# pcblayout.net
KiCad netlist of a schematic drawn in Altium Designer
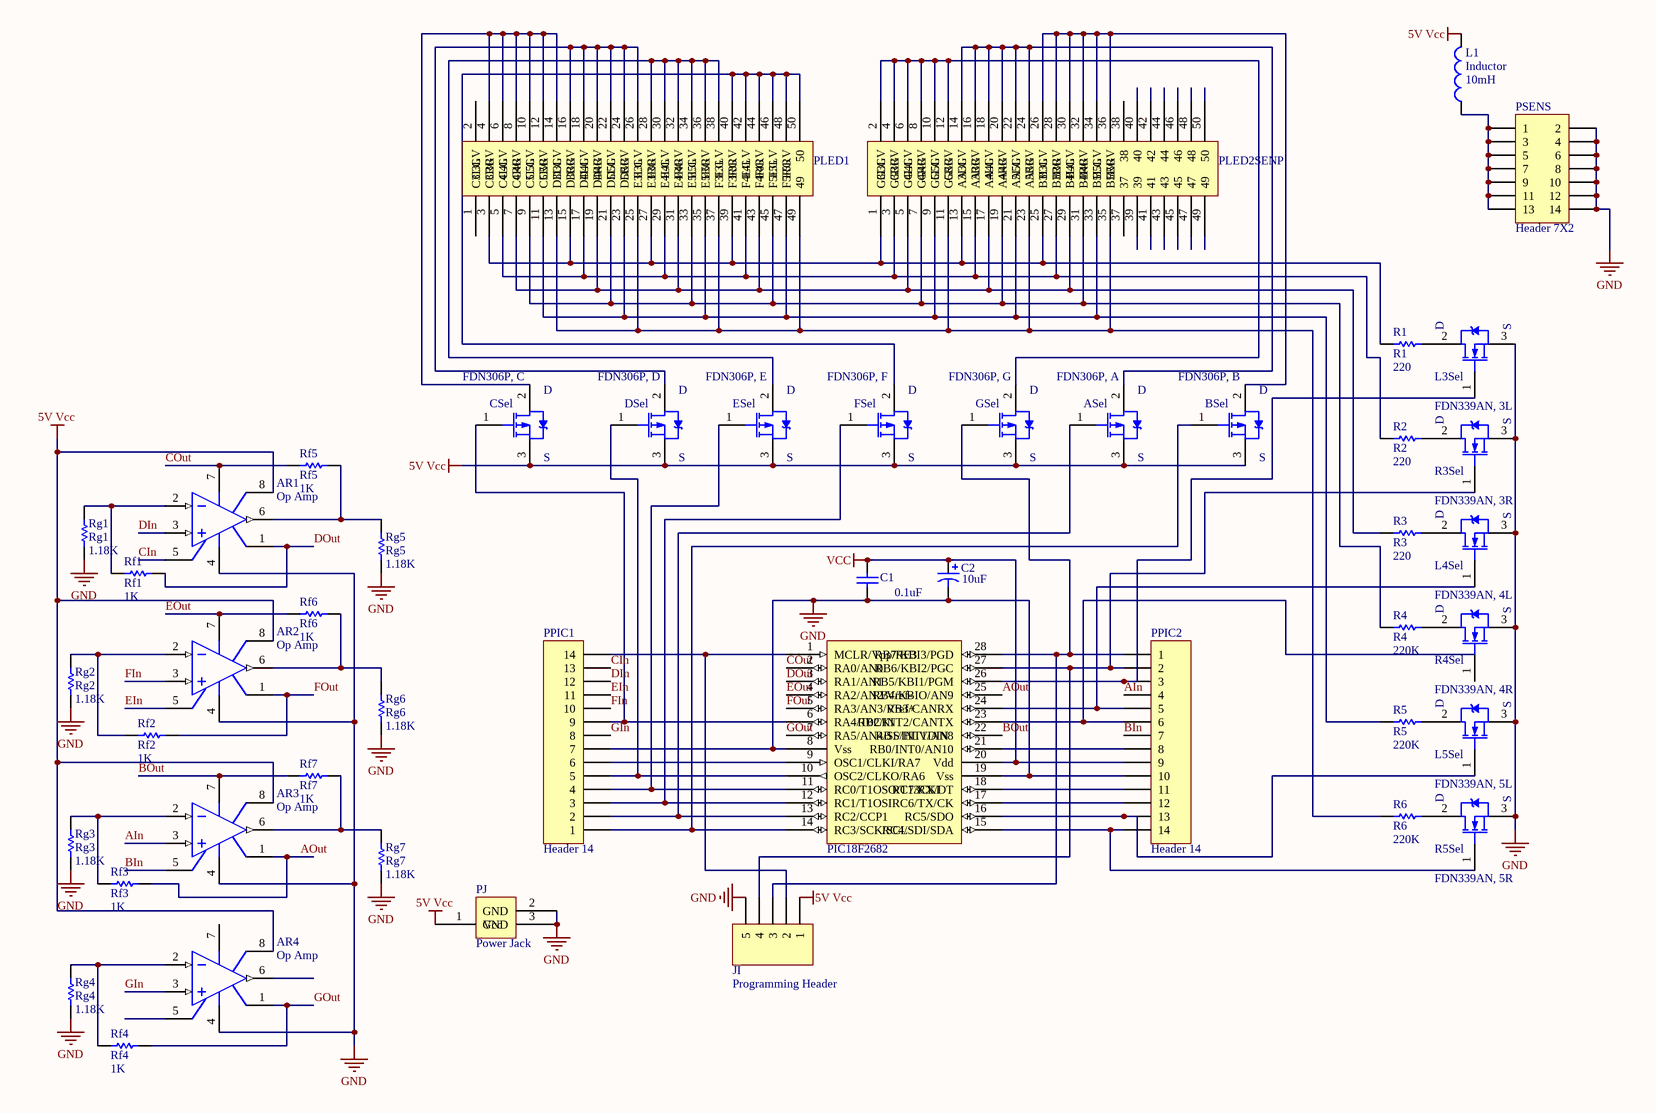
[diagram p0: pcblayout.SchDoc]

(export (version "E")
  (design (tool "Eeschema 10.0.6"))
  (components
    (comp (ref "AR1")
      (value "Op Amp")
      (footprint "SOIC127P600X175-8N")
      (description "FET Operational Amplifier")
      (fields (field (name "PUBLISHER") "Altium Limited"))
      (libsource (lib "Miscellaneous Devices") (part "Op Amp"))
    )
    (comp (ref "AR2")
      (value "Op Amp")
      (footprint "SOIC127P600X175-8N")
      (description "FET Operational Amplifier")
      (fields (field (name "PUBLISHER") "Altium Limited"))
      (libsource (lib "Miscellaneous Devices") (part "Op Amp"))
    )
    (comp (ref "AR3")
      (value "Op Amp")
      (footprint "SOIC127P600X175-8N")
      (description "FET Operational Amplifier")
      (fields (field (name "PUBLISHER") "Altium Limited"))
      (libsource (lib "Miscellaneous Devices") (part "Op Amp"))
    )
    (comp (ref "AR4")
      (value "Op Amp")
      (footprint "SOIC127P600X175-8N")
      (description "FET Operational Amplifier")
      (fields (field (name "PUBLISHER") "Altium Limited"))
      (libsource (lib "Miscellaneous Devices") (part "Op Amp"))
    )
    (comp (ref "ASel")
      (value "FDN306P, A")
      (footprint "SOT23-3M")
      (description "Pch MOSFET")
      (libsource (lib "pcbLib") (part "FDN304P"))
    )
    (comp (ref "BSel")
      (value "FDN306P, B")
      (footprint "SOT23-3M")
      (description "Pch MOSFET")
      (libsource (lib "pcbLib") (part "FDN304P"))
    )
    (comp (ref "C1")
      (value "0.1uF")
      (footprint "CAPC2012M")
      (description "Capacitor")
      (fields (field (name "Comment") "Cap") (field (name "PUBLISHER") "Altium Limited"))
      (libsource (lib "Miscellaneous Devices") (part "Cap"))
    )
    (comp (ref "C2")
      (value "10uF")
      (footprint "TC3216-1206")
      (description "Polarized Capacitor (Radial)")
      (fields (field (name "Comment") "Cap Pol1") (field (name "PUBLISHER") "Altium Limited"))
      (libsource (lib "Miscellaneous Devices") (part "Cap Pol1"))
    )
    (comp (ref "CSel")
      (value "FDN306P, C")
      (footprint "SOT23-3M")
      (description "Pch MOSFET")
      (libsource (lib "pcbLib") (part "FDN304P"))
    )
    (comp (ref "DSel")
      (value "FDN306P, D")
      (footprint "SOT23-3M")
      (description "Pch MOSFET")
      (libsource (lib "pcbLib") (part "FDN304P"))
    )
    (comp (ref "ESel")
      (value "FDN306P, E")
      (footprint "SOT23-3M")
      (description "Pch MOSFET")
      (libsource (lib "pcbLib") (part "FDN304P"))
    )
    (comp (ref "FSel")
      (value "FDN306P, F")
      (footprint "SOT23-3M")
      (description "Pch MOSFET")
      (libsource (lib "pcbLib") (part "FDN304P"))
    )
    (comp (ref "GSel")
      (value "FDN306P, G")
      (footprint "SOT23-3M")
      (description "Pch MOSFET")
      (libsource (lib "pcbLib") (part "FDN304P"))
    )
    (comp (ref "JI")
      (value "Programming Header")
      (footprint "HDR1X5")
      (description "Header, 5-Pin")
      (fields (field (name "PUBLISHER") "Altium Limited"))
      (libsource (lib "Miscellaneous Connectors") (part "Header 5"))
    )
    (comp (ref "L1")
      (value "Inductor")
      (footprint "INDC2012M")
      (fields (field (name "ALTIUM_VALUE") "10mH") (field (name "PUBLISHER") "Altium Limited"))
      (libsource (lib "Miscellaneous Devices") (part "Inductor"))
    )
    (comp (ref "L3Sel")
      (value "FDN339AN, 3L")
      (footprint "SOT23-3M")
      (description "Nch MOSFET")
      (libsource (lib "pcbLib") (part "FDN339AN"))
    )
    (comp (ref "L4Sel")
      (value "FDN339AN, 4L")
      (footprint "SOT23-3M")
      (description "Nch MOSFET")
      (libsource (lib "pcbLib") (part "FDN339AN"))
    )
    (comp (ref "L5Sel")
      (value "FDN339AN, 5L")
      (footprint "SOT23-3M")
      (description "Nch MOSFET")
      (libsource (lib "pcbLib") (part "FDN339AN"))
    )
    (comp (ref "PIC18F2682")
      (value "PIC18F2682")
      (footprint "DIP28")
      (libsource (lib "pcbLib") (part "PIC18F2682"))
    )
    (comp (ref "PJ")
      (value "Power Jack")
      (footprint "BARREL JACK")
      (libsource (lib "pcbLib") (part "Power Jack"))
    )
    (comp (ref "PLED1")
      (value "50x2 Pin Header, PLED1")
      (footprint "HDR2X25")
      (libsource (lib "pcbLib") (part "50x2 Pin Header, PLED1"))
    )
    (comp (ref "PLED2SENP")
      (value "50x2 Pin Header, PLED2SENP")
      (footprint "HDR2X25")
      (libsource (lib "pcbLib") (part "50x2 Pin Header, PLED2SENP"))
    )
    (comp (ref "PPIC1")
      (value "Header 14")
      (footprint "HDR1X14")
      (description "Header, 14-Pin")
      (fields (field (name "PUBLISHER") "Altium Limited"))
      (libsource (lib "") (part "Header 14_1"))
    )
    (comp (ref "PPIC2")
      (value "Header 14")
      (footprint "HDR1X14")
      (description "Header, 14-Pin")
      (fields (field (name "PUBLISHER") "Altium Limited"))
      (libsource (lib "Miscellaneous Connectors") (part "Header 14"))
    )
    (comp (ref "PSENS")
      (value "Header 7X2")
      (footprint "HDR2X7")
      (description "Header, 7-Pin, Dual row")
      (fields (field (name "PUBLISHER") "Altium Limited"))
      (libsource (lib "Miscellaneous Connectors") (part "Header 7X2"))
    )
    (comp (ref "R1")
      (value "R1")
      (footprint "RESC2012M")
      (description "Resistor")
      (fields (field (name "ALTIUM_VALUE") "220") (field (name "PUBLISHER") "Altium Limited"))
      (libsource (lib "Miscellaneous Devices") (part "Res1"))
    )
    (comp (ref "R2")
      (value "R2")
      (footprint "RESC2012M")
      (description "Resistor")
      (fields (field (name "ALTIUM_VALUE") "220") (field (name "PUBLISHER") "Altium Limited"))
      (libsource (lib "Miscellaneous Devices") (part "Res1"))
    )
    (comp (ref "R3")
      (value "R3")
      (footprint "RESC2012M")
      (description "Resistor")
      (fields (field (name "ALTIUM_VALUE") "220") (field (name "PUBLISHER") "Altium Limited"))
      (libsource (lib "Miscellaneous Devices") (part "Res1"))
    )
    (comp (ref "R3Sel")
      (value "FDN339AN, 3R")
      (footprint "SOT23-3M")
      (description "Nch MOSFET")
      (libsource (lib "pcbLib") (part "FDN339AN"))
    )
    (comp (ref "R4")
      (value "R4")
      (footprint "RESC2012M")
      (description "Resistor")
      (fields (field (name "ALTIUM_VALUE") "220K") (field (name "PUBLISHER") "Altium Limited"))
      (libsource (lib "Miscellaneous Devices") (part "Res1"))
    )
    (comp (ref "R4Sel")
      (value "FDN339AN, 4R")
      (footprint "SOT23-3M")
      (description "Nch MOSFET")
      (libsource (lib "pcbLib") (part "FDN339AN"))
    )
    (comp (ref "R5")
      (value "R5")
      (footprint "RESC2012M")
      (description "Resistor")
      (fields (field (name "ALTIUM_VALUE") "220K") (field (name "PUBLISHER") "Altium Limited"))
      (libsource (lib "Miscellaneous Devices") (part "Res1"))
    )
    (comp (ref "R5Sel")
      (value "FDN339AN, 5R")
      (footprint "SOT23-3M")
      (description "Nch MOSFET")
      (libsource (lib "pcbLib") (part "FDN339AN"))
    )
    (comp (ref "R6")
      (value "R6")
      (footprint "RESC2012M")
      (description "Resistor")
      (fields (field (name "ALTIUM_VALUE") "220K") (field (name "PUBLISHER") "Altium Limited"))
      (libsource (lib "Miscellaneous Devices") (part "Res1"))
    )
    (comp (ref "Rf1")
      (value "Rf1")
      (footprint "RESC2012M")
      (description "Resistor")
      (fields (field (name "ALTIUM_VALUE") "1K") (field (name "PUBLISHER") "Altium Limited"))
      (libsource (lib "Miscellaneous Devices") (part "Res1"))
    )
    (comp (ref "Rf2")
      (value "Rf2")
      (footprint "RESC2012M")
      (description "Resistor")
      (fields (field (name "ALTIUM_VALUE") "1K") (field (name "PUBLISHER") "Altium Limited"))
      (libsource (lib "Miscellaneous Devices") (part "Res1"))
    )
    (comp (ref "Rf3")
      (value "Rf3")
      (footprint "RESC2012M")
      (description "Resistor")
      (fields (field (name "ALTIUM_VALUE") "1K") (field (name "PUBLISHER") "Altium Limited"))
      (libsource (lib "Miscellaneous Devices") (part "Res1"))
    )
    (comp (ref "Rf4")
      (value "Rf4")
      (footprint "RESC2012M")
      (description "Resistor")
      (fields (field (name "ALTIUM_VALUE") "1K") (field (name "PUBLISHER") "Altium Limited"))
      (libsource (lib "Miscellaneous Devices") (part "Res1"))
    )
    (comp (ref "Rf5")
      (value "Rf5")
      (footprint "RESC2012M")
      (description "Resistor")
      (fields (field (name "ALTIUM_VALUE") "1K") (field (name "PUBLISHER") "Altium Limited"))
      (libsource (lib "Miscellaneous Devices") (part "Res1"))
    )
    (comp (ref "Rf6")
      (value "Rf6")
      (footprint "RESC2012M")
      (description "Resistor")
      (fields (field (name "ALTIUM_VALUE") "1K") (field (name "PUBLISHER") "Altium Limited"))
      (libsource (lib "Miscellaneous Devices") (part "Res1"))
    )
    (comp (ref "Rf7")
      (value "Rf7")
      (footprint "RESC2012M")
      (description "Resistor")
      (fields (field (name "ALTIUM_VALUE") "1K") (field (name "PUBLISHER") "Altium Limited"))
      (libsource (lib "Miscellaneous Devices") (part "Res1"))
    )
    (comp (ref "Rg1")
      (value "Rg1")
      (footprint "RESC2012M")
      (description "Resistor")
      (fields (field (name "ALTIUM_VALUE") "1.18K") (field (name "PUBLISHER") "Altium Limited"))
      (libsource (lib "Miscellaneous Devices") (part "Res1"))
    )
    (comp (ref "Rg2")
      (value "Rg2")
      (footprint "RESC2012M")
      (description "Resistor")
      (fields (field (name "ALTIUM_VALUE") "1.18K") (field (name "PUBLISHER") "Altium Limited"))
      (libsource (lib "Miscellaneous Devices") (part "Res1"))
    )
    (comp (ref "Rg3")
      (value "Rg3")
      (footprint "RESC2012M")
      (description "Resistor")
      (fields (field (name "ALTIUM_VALUE") "1.18K") (field (name "PUBLISHER") "Altium Limited"))
      (libsource (lib "Miscellaneous Devices") (part "Res1"))
    )
    (comp (ref "Rg4")
      (value "Rg4")
      (footprint "RESC2012M")
      (description "Resistor")
      (fields (field (name "ALTIUM_VALUE") "1.18K") (field (name "PUBLISHER") "Altium Limited"))
      (libsource (lib "Miscellaneous Devices") (part "Res1"))
    )
    (comp (ref "Rg5")
      (value "Rg5")
      (footprint "RESC2012M")
      (description "Resistor")
      (fields (field (name "ALTIUM_VALUE") "1.18K") (field (name "PUBLISHER") "Altium Limited"))
      (libsource (lib "Miscellaneous Devices") (part "Res1"))
    )
    (comp (ref "Rg6")
      (value "Rg6")
      (footprint "RESC2012M")
      (description "Resistor")
      (fields (field (name "ALTIUM_VALUE") "1.18K") (field (name "PUBLISHER") "Altium Limited"))
      (libsource (lib "Miscellaneous Devices") (part "Res1"))
    )
    (comp (ref "Rg7")
      (value "Rg7")
      (footprint "RESC2012M")
      (description "Resistor")
      (fields (field (name "ALTIUM_VALUE") "1.18K") (field (name "PUBLISHER") "Altium Limited"))
      (libsource (lib "Miscellaneous Devices") (part "Res1"))
    )
  )
  (nets
    (net (code "1") (name "/AIn") (class "Default")
      (node (ref "AR3") (pin "3") (pinfunction "IN+_3") (pintype "input"))
      (node (ref "PPIC2") (pin "4") (pinfunction "4_4") (pintype "passive"))
    )
    (net (code "2") (name "/AOut") (class "Default")
      (node (ref "AR3") (pin "1") (pinfunction "OS_NUL_1") (pintype "passive"))
      (node (ref "PIC18F2682") (pin "25") (pinfunction "RB4/KBIO/AN9_25") (pintype "bidirectional"))
      (node (ref "Rf3") (pin "2") (pinfunction "2_2") (pintype "passive"))
    )
    (net (code "3") (name "/BIn") (class "Default")
      (node (ref "AR3") (pin "5") (pinfunction "OS_NUL_5") (pintype "passive"))
      (node (ref "PPIC2") (pin "7") (pinfunction "7_7") (pintype "passive"))
    )
    (net (code "4") (name "/BOut") (class "Default")
      (node (ref "AR3") (pin "7") (pinfunction "V+_7") (pintype "power_in"))
      (node (ref "PIC18F2682") (pin "22") (pinfunction "RB1/INT1/AN8_22") (pintype "bidirectional"))
      (node (ref "Rf7") (pin "1") (pinfunction "1_1") (pintype "passive"))
    )
    (net (code "5") (name "/CIn") (class "Default")
      (node (ref "AR1") (pin "5") (pinfunction "OS_NUL_5") (pintype "passive"))
      (node (ref "PPIC1") (pin "13") (pinfunction "13_13") (pintype "passive"))
    )
    (net (code "6") (name "/COut") (class "Default")
      (node (ref "AR1") (pin "7") (pinfunction "V+_7") (pintype "power_in"))
      (node (ref "PIC18F2682") (pin "2") (pinfunction "RA0/AN0_2") (pintype "bidirectional"))
      (node (ref "Rf5") (pin "1") (pinfunction "1_1") (pintype "passive"))
    )
    (net (code "7") (name "/DIn") (class "Default")
      (node (ref "AR1") (pin "3") (pinfunction "IN+_3") (pintype "input"))
      (node (ref "PPIC1") (pin "12") (pinfunction "12_12") (pintype "passive"))
    )
    (net (code "8") (name "/DOut") (class "Default")
      (node (ref "AR1") (pin "1") (pinfunction "OS_NUL_1") (pintype "passive"))
      (node (ref "PIC18F2682") (pin "3") (pinfunction "RA1/AN1_3") (pintype "bidirectional"))
      (node (ref "Rf1") (pin "2") (pinfunction "2_2") (pintype "passive"))
    )
    (net (code "9") (name "/EIn") (class "Default")
      (node (ref "AR2") (pin "5") (pinfunction "OS_NUL_5") (pintype "passive"))
      (node (ref "PPIC1") (pin "11") (pinfunction "11_11") (pintype "passive"))
    )
    (net (code "10") (name "/EOut") (class "Default")
      (node (ref "AR2") (pin "7") (pinfunction "V+_7") (pintype "power_in"))
      (node (ref "PIC18F2682") (pin "4") (pinfunction "RA2/AN2/Vref-_4") (pintype "bidirectional"))
      (node (ref "Rf6") (pin "1") (pinfunction "1_1") (pintype "passive"))
    )
    (net (code "11") (name "/FIn") (class "Default")
      (node (ref "AR2") (pin "3") (pinfunction "IN+_3") (pintype "input"))
      (node (ref "PPIC1") (pin "10") (pinfunction "10_10") (pintype "passive"))
    )
    (net (code "12") (name "/FOut") (class "Default")
      (node (ref "AR2") (pin "1") (pinfunction "OS_NUL_1") (pintype "passive"))
      (node (ref "PIC18F2682") (pin "5") (pinfunction "RA3/AN3/Vref+_5") (pintype "bidirectional"))
      (node (ref "Rf2") (pin "2") (pinfunction "2_2") (pintype "passive"))
    )
    (net (code "13") (name "/GIn") (class "Default")
      (node (ref "AR4") (pin "3") (pinfunction "IN+_3") (pintype "input"))
      (node (ref "PPIC1") (pin "8") (pinfunction "8_8") (pintype "passive"))
    )
    (net (code "14") (name "/GOut") (class "Default")
      (node (ref "AR4") (pin "1") (pinfunction "OS_NUL_1") (pintype "passive"))
      (node (ref "PIC18F2682") (pin "7") (pinfunction "RA5/AN4/SS/HLVDIN_7") (pintype "bidirectional"))
      (node (ref "Rf4") (pin "2") (pinfunction "2_2") (pintype "passive"))
    )
    (net (code "15") (name "5V Vcc") (class "Default")
      (node (ref "AR1") (pin "8") (pinfunction "TAB_8") (pintype "passive"))
      (node (ref "AR2") (pin "8") (pinfunction "TAB_8") (pintype "passive"))
      (node (ref "AR3") (pin "8") (pinfunction "TAB_8") (pintype "passive"))
      (node (ref "AR4") (pin "8") (pinfunction "TAB_8") (pintype "passive"))
      (node (ref "ASel") (pin "3") (pinfunction "S_3") (pintype "passive"))
      (node (ref "BSel") (pin "3") (pinfunction "S_3") (pintype "passive"))
      (node (ref "CSel") (pin "3") (pinfunction "S_3") (pintype "passive"))
      (node (ref "DSel") (pin "3") (pinfunction "S_3") (pintype "passive"))
      (node (ref "ESel") (pin "3") (pinfunction "S_3") (pintype "passive"))
      (node (ref "FSel") (pin "3") (pinfunction "S_3") (pintype "passive"))
      (node (ref "GSel") (pin "3") (pinfunction "S_3") (pintype "passive"))
      (node (ref "JI") (pin "1") (pinfunction "1_1") (pintype "passive"))
      (node (ref "L1") (pin "2") (pinfunction "2_2") (pintype "passive"))
      (node (ref "PJ") (pin "1") (pinfunction "Vcc_1") (pintype "passive"))
    )
    (net (code "16") (name "GND") (class "Default")
      (node (ref "AR1") (pin "4") (pinfunction "V-_4") (pintype "power_in"))
      (node (ref "AR2") (pin "4") (pinfunction "V-_4") (pintype "power_in"))
      (node (ref "AR3") (pin "4") (pinfunction "V-_4") (pintype "power_in"))
      (node (ref "AR4") (pin "4") (pinfunction "V-_4") (pintype "power_in"))
      (node (ref "C1") (pin "1") (pinfunction "1_1") (pintype "passive"))
      (node (ref "C2") (pin "2") (pinfunction "2_2") (pintype "passive"))
      (node (ref "JI") (pin "5") (pinfunction "5_5") (pintype "passive"))
      (node (ref "L3Sel") (pin "3") (pinfunction "S_3") (pintype "passive"))
      (node (ref "L4Sel") (pin "3") (pinfunction "S_3") (pintype "passive"))
      (node (ref "L5Sel") (pin "3") (pinfunction "S_3") (pintype "passive"))
      (node (ref "PIC18F2682") (pin "19") (pinfunction "Vss_19") (pintype "power_in"))
      (node (ref "PIC18F2682") (pin "8") (pinfunction "Vss_8") (pintype "power_in"))
      (node (ref "PJ") (pin "2") (pinfunction "GND_2") (pintype "passive"))
      (node (ref "PJ") (pin "3") (pinfunction "GND_3") (pintype "passive"))
      (node (ref "PPIC1") (pin "7") (pinfunction "7_7") (pintype "passive"))
      (node (ref "PPIC2") (pin "10") (pinfunction "10_10") (pintype "passive"))
      (node (ref "PSENS") (pin "10") (pinfunction "10_10") (pintype "passive"))
      (node (ref "PSENS") (pin "12") (pinfunction "12_12") (pintype "passive"))
      (node (ref "PSENS") (pin "14") (pinfunction "14_14") (pintype "passive"))
      (node (ref "PSENS") (pin "2") (pinfunction "2_2") (pintype "passive"))
      (node (ref "PSENS") (pin "4") (pinfunction "4_4") (pintype "passive"))
      (node (ref "PSENS") (pin "6") (pinfunction "6_6") (pintype "passive"))
      (node (ref "PSENS") (pin "8") (pinfunction "8_8") (pintype "passive"))
      (node (ref "R3Sel") (pin "3") (pinfunction "S_3") (pintype "passive"))
      (node (ref "R4Sel") (pin "3") (pinfunction "S_3") (pintype "passive"))
      (node (ref "R5Sel") (pin "3") (pinfunction "S_3") (pintype "passive"))
      (node (ref "Rg1") (pin "1") (pinfunction "1_1") (pintype "passive"))
      (node (ref "Rg2") (pin "2") (pinfunction "2_2") (pintype "passive"))
      (node (ref "Rg3") (pin "1") (pinfunction "1_1") (pintype "passive"))
      (node (ref "Rg4") (pin "1") (pinfunction "1_1") (pintype "passive"))
      (node (ref "Rg5") (pin "1") (pinfunction "1_1") (pintype "passive"))
      (node (ref "Rg6") (pin "1") (pinfunction "1_1") (pintype "passive"))
      (node (ref "Rg7") (pin "1") (pinfunction "1_1") (pintype "passive"))
    )
    (net (code "17") (name "Net-(AR1-IN-)") (class "Default")
      (node (ref "AR1") (pin "2") (pinfunction "IN-_2") (pintype "input"))
      (node (ref "Rf1") (pin "1") (pinfunction "1_1") (pintype "passive"))
      (node (ref "Rg1") (pin "2") (pinfunction "2_2") (pintype "passive"))
    )
    (net (code "18") (name "Net-(AR1-OUT)") (class "Default")
      (node (ref "AR1") (pin "6") (pinfunction "OUT_6") (pintype "output"))
      (node (ref "Rf5") (pin "2") (pinfunction "2_2") (pintype "passive"))
      (node (ref "Rg5") (pin "2") (pinfunction "2_2") (pintype "passive"))
    )
    (net (code "19") (name "Net-(AR2-IN-)") (class "Default")
      (node (ref "AR2") (pin "2") (pinfunction "IN-_2") (pintype "input"))
      (node (ref "Rf2") (pin "1") (pinfunction "1_1") (pintype "passive"))
      (node (ref "Rg2") (pin "1") (pinfunction "1_1") (pintype "passive"))
    )
    (net (code "20") (name "Net-(AR2-OUT)") (class "Default")
      (node (ref "AR2") (pin "6") (pinfunction "OUT_6") (pintype "output"))
      (node (ref "Rf6") (pin "2") (pinfunction "2_2") (pintype "passive"))
      (node (ref "Rg6") (pin "2") (pinfunction "2_2") (pintype "passive"))
    )
    (net (code "21") (name "Net-(AR3-IN-)") (class "Default")
      (node (ref "AR3") (pin "2") (pinfunction "IN-_2") (pintype "input"))
      (node (ref "Rf3") (pin "1") (pinfunction "1_1") (pintype "passive"))
      (node (ref "Rg3") (pin "2") (pinfunction "2_2") (pintype "passive"))
    )
    (net (code "22") (name "Net-(AR3-OUT)") (class "Default")
      (node (ref "AR3") (pin "6") (pinfunction "OUT_6") (pintype "output"))
      (node (ref "Rf7") (pin "2") (pinfunction "2_2") (pintype "passive"))
      (node (ref "Rg7") (pin "2") (pinfunction "2_2") (pintype "passive"))
    )
    (net (code "23") (name "Net-(AR4-IN-)") (class "Default")
      (node (ref "AR4") (pin "2") (pinfunction "IN-_2") (pintype "input"))
      (node (ref "Rf4") (pin "1") (pinfunction "1_1") (pintype "passive"))
      (node (ref "Rg4") (pin "2") (pinfunction "2_2") (pintype "passive"))
    )
    (net (code "24") (name "Net-(ASel-D)") (class "Default")
      (node (ref "ASel") (pin "2") (pinfunction "D_2") (pintype "passive"))
      (node (ref "PLED2SENP") (pin "14") (pinfunction "A3LV_14") (pintype "passive"))
      (node (ref "PLED2SENP") (pin "16") (pinfunction "A3RV_16") (pintype "passive"))
      (node (ref "PLED2SENP") (pin "18") (pinfunction "A4LV_18") (pintype "passive"))
      (node (ref "PLED2SENP") (pin "20") (pinfunction "A4RV_20") (pintype "passive"))
      (node (ref "PLED2SENP") (pin "22") (pinfunction "A5LV_22") (pintype "passive"))
      (node (ref "PLED2SENP") (pin "24") (pinfunction "A5RV_24") (pintype "passive"))
    )
    (net (code "25") (name "Net-(ASel-G)") (class "Default")
      (node (ref "ASel") (pin "1") (pinfunction "G_1") (pintype "passive"))
      (node (ref "PIC18F2682") (pin "13") (pinfunction "RC2/CCP1_13") (pintype "bidirectional"))
      (node (ref "PPIC1") (pin "2") (pinfunction "2_2") (pintype "passive"))
    )
    (net (code "26") (name "Net-(BSel-D)") (class "Default")
      (node (ref "BSel") (pin "2") (pinfunction "D_2") (pintype "passive"))
      (node (ref "PLED2SENP") (pin "26") (pinfunction "B3LV_26") (pintype "passive"))
      (node (ref "PLED2SENP") (pin "28") (pinfunction "B3RV_28") (pintype "passive"))
      (node (ref "PLED2SENP") (pin "30") (pinfunction "B4LV_30") (pintype "passive"))
      (node (ref "PLED2SENP") (pin "32") (pinfunction "B4RV_32") (pintype "passive"))
      (node (ref "PLED2SENP") (pin "34") (pinfunction "B5LV_34") (pintype "passive"))
      (node (ref "PLED2SENP") (pin "36") (pinfunction "B5RV_36") (pintype "passive"))
    )
    (net (code "27") (name "Net-(BSel-G)") (class "Default")
      (node (ref "BSel") (pin "1") (pinfunction "G_1") (pintype "passive"))
      (node (ref "PIC18F2682") (pin "14") (pinfunction "RC3/SCK/SCL_14") (pintype "bidirectional"))
      (node (ref "PPIC1") (pin "1") (pinfunction "1_1") (pintype "passive"))
    )
    (net (code "28") (name "Net-(CSel-D)") (class "Default")
      (node (ref "CSel") (pin "2") (pinfunction "D_2") (pintype "passive"))
      (node (ref "PLED1") (pin "10") (pinfunction "C5LV_10") (pintype "passive"))
      (node (ref "PLED1") (pin "12") (pinfunction "C5RV_12") (pintype "passive"))
      (node (ref "PLED1") (pin "14") (pinfunction "D3LV_14") (pintype "passive"))
      (node (ref "PLED1") (pin "4") (pinfunction "C3RV_4") (pintype "passive"))
      (node (ref "PLED1") (pin "6") (pinfunction "C4LV_6") (pintype "passive"))
      (node (ref "PLED1") (pin "8") (pinfunction "C4RV_8") (pintype "passive"))
    )
    (net (code "29") (name "Net-(CSel-G)") (class "Default")
      (node (ref "CSel") (pin "1") (pinfunction "G_1") (pintype "passive"))
      (node (ref "PIC18F2682") (pin "6") (pinfunction "RA4/T0CKI_6") (pintype "bidirectional"))
      (node (ref "PPIC1") (pin "9") (pinfunction "9_9") (pintype "passive"))
    )
    (net (code "30") (name "Net-(DSel-D)") (class "Default")
      (node (ref "DSel") (pin "2") (pinfunction "D_2") (pintype "passive"))
      (node (ref "PLED1") (pin "16") (pinfunction "D3RV_16") (pintype "passive"))
      (node (ref "PLED1") (pin "18") (pinfunction "D4LV_18") (pintype "passive"))
      (node (ref "PLED1") (pin "20") (pinfunction "D4RV_20") (pintype "passive"))
      (node (ref "PLED1") (pin "22") (pinfunction "D5LV_22") (pintype "passive"))
      (node (ref "PLED1") (pin "24") (pinfunction "D5RV_24") (pintype "passive"))
      (node (ref "PLED1") (pin "26") (pinfunction "E3LV_26") (pintype "passive"))
    )
    (net (code "31") (name "Net-(DSel-G)") (class "Default")
      (node (ref "DSel") (pin "1") (pinfunction "G_1") (pintype "passive"))
      (node (ref "PIC18F2682") (pin "10") (pinfunction "OSC2/CLKO/RA6_10") (pintype "output"))
      (node (ref "PPIC1") (pin "5") (pinfunction "5_5") (pintype "passive"))
    )
    (net (code "32") (name "Net-(ESel-D)") (class "Default")
      (node (ref "ESel") (pin "2") (pinfunction "D_2") (pintype "passive"))
      (node (ref "PLED1") (pin "28") (pinfunction "E3RV_28") (pintype "passive"))
      (node (ref "PLED1") (pin "30") (pinfunction "E4LV_30") (pintype "passive"))
      (node (ref "PLED1") (pin "32") (pinfunction "E4RV_32") (pintype "passive"))
      (node (ref "PLED1") (pin "34") (pinfunction "E5LV_34") (pintype "passive"))
      (node (ref "PLED1") (pin "36") (pinfunction "E5RV_36") (pintype "passive"))
      (node (ref "PLED1") (pin "38") (pinfunction "F3LV_38") (pintype "passive"))
    )
    (net (code "33") (name "Net-(ESel-G)") (class "Default")
      (node (ref "ESel") (pin "1") (pinfunction "G_1") (pintype "passive"))
      (node (ref "PIC18F2682") (pin "11") (pinfunction "RC0/T1OSO/T13CKI_11") (pintype "bidirectional"))
      (node (ref "PPIC1") (pin "4") (pinfunction "4_4") (pintype "passive"))
    )
    (net (code "34") (name "Net-(FSel-D)") (class "Default")
      (node (ref "FSel") (pin "2") (pinfunction "D_2") (pintype "passive"))
      (node (ref "PLED1") (pin "40") (pinfunction "F3RV_40") (pintype "passive"))
      (node (ref "PLED1") (pin "42") (pinfunction "F4LV_42") (pintype "passive"))
      (node (ref "PLED1") (pin "44") (pinfunction "F4RV_44") (pintype "passive"))
      (node (ref "PLED1") (pin "46") (pinfunction "F5LV_46") (pintype "passive"))
      (node (ref "PLED1") (pin "48") (pinfunction "F5RV_48") (pintype "passive"))
      (node (ref "PLED1") (pin "50") (pinfunction "50_50") (pintype "passive"))
    )
    (net (code "35") (name "Net-(FSel-G)") (class "Default")
      (node (ref "FSel") (pin "1") (pinfunction "G_1") (pintype "passive"))
      (node (ref "PIC18F2682") (pin "12") (pinfunction "RC1/T1OSI_12") (pintype "bidirectional"))
      (node (ref "PPIC1") (pin "3") (pinfunction "3_3") (pintype "passive"))
    )
    (net (code "36") (name "Net-(GSel-D)") (class "Default")
      (node (ref "GSel") (pin "2") (pinfunction "D_2") (pintype "passive"))
      (node (ref "PLED2SENP") (pin "10") (pinfunction "G5LV_10") (pintype "passive"))
      (node (ref "PLED2SENP") (pin "12") (pinfunction "G5RV_12") (pintype "passive"))
      (node (ref "PLED2SENP") (pin "2") (pinfunction "G3LV_2") (pintype "passive"))
      (node (ref "PLED2SENP") (pin "4") (pinfunction "G3RV_4") (pintype "passive"))
      (node (ref "PLED2SENP") (pin "6") (pinfunction "G4LV_6") (pintype "passive"))
      (node (ref "PLED2SENP") (pin "8") (pinfunction "G4RV_8") (pintype "passive"))
    )
    (net (code "37") (name "Net-(GSel-G)") (class "Default")
      (node (ref "GSel") (pin "1") (pinfunction "G_1") (pintype "passive"))
      (node (ref "JI") (pin "3") (pinfunction "3_3") (pintype "passive"))
      (node (ref "PIC18F2682") (pin "28") (pinfunction "RB7/KBI3/PGD_28") (pintype "bidirectional"))
      (node (ref "PPIC2") (pin "1") (pinfunction "1_1") (pintype "passive"))
    )
    (net (code "38") (name "Net-(L1-Pad1)") (class "Default")
      (node (ref "L1") (pin "1") (pinfunction "1_1") (pintype "passive"))
      (node (ref "PSENS") (pin "1") (pinfunction "1_1") (pintype "passive"))
      (node (ref "PSENS") (pin "11") (pinfunction "11_11") (pintype "passive"))
      (node (ref "PSENS") (pin "13") (pinfunction "13_13") (pintype "passive"))
      (node (ref "PSENS") (pin "3") (pinfunction "3_3") (pintype "passive"))
      (node (ref "PSENS") (pin "5") (pinfunction "5_5") (pintype "passive"))
      (node (ref "PSENS") (pin "7") (pinfunction "7_7") (pintype "passive"))
      (node (ref "PSENS") (pin "9") (pinfunction "9_9") (pintype "passive"))
    )
    (net (code "39") (name "Net-(L3Sel-D)") (class "Default")
      (node (ref "L3Sel") (pin "2") (pinfunction "D_2") (pintype "passive"))
      (node (ref "R1") (pin "2") (pinfunction "2_2") (pintype "passive"))
    )
    (net (code "40") (name "Net-(L3Sel-G)") (class "Default")
      (node (ref "L3Sel") (pin "1") (pinfunction "G_1") (pintype "passive"))
      (node (ref "PIC18F2682") (pin "26") (pinfunction "RB5/KBI1/PGM_26") (pintype "bidirectional"))
      (node (ref "PPIC2") (pin "3") (pinfunction "3_3") (pintype "passive"))
    )
    (net (code "41") (name "Net-(L4Sel-D)") (class "Default")
      (node (ref "L4Sel") (pin "2") (pinfunction "D_2") (pintype "passive"))
      (node (ref "R3") (pin "2") (pinfunction "2_2") (pintype "passive"))
    )
    (net (code "42") (name "Net-(L4Sel-G)") (class "Default")
      (node (ref "L4Sel") (pin "1") (pinfunction "G_1") (pintype "passive"))
      (node (ref "PIC18F2682") (pin "24") (pinfunction "RB3/CANRX_24") (pintype "bidirectional"))
      (node (ref "PPIC2") (pin "5") (pinfunction "5_5") (pintype "passive"))
    )
    (net (code "43") (name "Net-(L5Sel-D)") (class "Default")
      (node (ref "L5Sel") (pin "2") (pinfunction "D_2") (pintype "passive"))
      (node (ref "R5") (pin "2") (pinfunction "2_2") (pintype "passive"))
    )
    (net (code "44") (name "Net-(L5Sel-G)") (class "Default")
      (node (ref "L5Sel") (pin "1") (pinfunction "G_1") (pintype "passive"))
      (node (ref "PIC18F2682") (pin "16") (pinfunction "RC5/SDO_16") (pintype "bidirectional"))
      (node (ref "PPIC2") (pin "13") (pinfunction "13_13") (pintype "passive"))
    )
    (net (code "45") (name "Net-(PIC18F2682-MCLR{slash}Vpp{slash}RE3)") (class "Default")
      (node (ref "JI") (pin "2") (pinfunction "2_2") (pintype "passive"))
      (node (ref "PIC18F2682") (pin "1") (pinfunction "MCLR/Vpp/RE3_1") (pintype "input"))
      (node (ref "PPIC1") (pin "14") (pinfunction "14_14") (pintype "passive"))
    )
    (net (code "46") (name "Net-(PIC18F2682-OSC1{slash}CLKI{slash}RA7)") (class "Default")
      (node (ref "PIC18F2682") (pin "9") (pinfunction "OSC1/CLKI/RA7_9") (pintype "input"))
      (node (ref "PPIC1") (pin "6") (pinfunction "6_6") (pintype "passive"))
    )
    (net (code "47") (name "Net-(PIC18F2682-RB0{slash}INT0{slash}AN10)") (class "Default")
      (node (ref "PIC18F2682") (pin "21") (pinfunction "RB0/INT0/AN10_21") (pintype "bidirectional"))
      (node (ref "PPIC2") (pin "8") (pinfunction "8_8") (pintype "passive"))
    )
    (net (code "48") (name "Net-(PIC18F2682-RB2{slash}INT2{slash}CANTX)") (class "Default")
      (node (ref "PIC18F2682") (pin "23") (pinfunction "RB2/INT2/CANTX_23") (pintype "bidirectional"))
      (node (ref "PPIC2") (pin "6") (pinfunction "6_6") (pintype "passive"))
    )
    (net (code "49") (name "Net-(PIC18F2682-RB6{slash}KBI2{slash}PGC)") (class "Default")
      (node (ref "JI") (pin "4") (pinfunction "4_4") (pintype "passive"))
      (node (ref "PIC18F2682") (pin "27") (pinfunction "RB6/KBI2/PGC_27") (pintype "bidirectional"))
      (node (ref "PPIC2") (pin "2") (pinfunction "2_2") (pintype "passive"))
      (node (ref "R3Sel") (pin "1") (pinfunction "G_1") (pintype "passive"))
    )
    (net (code "50") (name "Net-(PIC18F2682-RC4{slash}SDI{slash}SDA)") (class "Default")
      (node (ref "PIC18F2682") (pin "15") (pinfunction "RC4/SDI/SDA_15") (pintype "bidirectional"))
      (node (ref "PPIC2") (pin "14") (pinfunction "14_14") (pintype "passive"))
      (node (ref "R5Sel") (pin "1") (pinfunction "G_1") (pintype "passive"))
    )
    (net (code "51") (name "Net-(PIC18F2682-RC6{slash}TX{slash}CK)") (class "Default")
      (node (ref "PIC18F2682") (pin "17") (pinfunction "RC6/TX/CK_17") (pintype "bidirectional"))
      (node (ref "PPIC2") (pin "12") (pinfunction "12_12") (pintype "passive"))
    )
    (net (code "52") (name "Net-(PIC18F2682-RC7{slash}RX{slash}DT)") (class "Default")
      (node (ref "PIC18F2682") (pin "18") (pinfunction "RC7/RX/DT_18") (pintype "bidirectional"))
      (node (ref "PPIC2") (pin "11") (pinfunction "11_11") (pintype "passive"))
    )
    (net (code "53") (name "Net-(PLED1-C3RG)") (class "Default")
      (node (ref "PLED1") (pin "15") (pinfunction "D3RG_15") (pintype "passive"))
      (node (ref "PLED1") (pin "27") (pinfunction "E3RG_27") (pintype "passive"))
      (node (ref "PLED1") (pin "3") (pinfunction "C3RG_3") (pintype "passive"))
      (node (ref "PLED1") (pin "39") (pinfunction "F3RG_39") (pintype "passive"))
      (node (ref "PLED2SENP") (pin "1") (pinfunction "G3LG_1") (pintype "passive"))
      (node (ref "PLED2SENP") (pin "13") (pinfunction "A3LG_13") (pintype "passive"))
      (node (ref "PLED2SENP") (pin "25") (pinfunction "B3LG_25") (pintype "passive"))
      (node (ref "R1") (pin "1") (pinfunction "1_1") (pintype "passive"))
    )
    (net (code "54") (name "Net-(PLED1-C4LG)") (class "Default")
      (node (ref "PLED1") (pin "17") (pinfunction "D4LG_17") (pintype "passive"))
      (node (ref "PLED1") (pin "29") (pinfunction "E4LG_29") (pintype "passive"))
      (node (ref "PLED1") (pin "41") (pinfunction "F4LG_41") (pintype "passive"))
      (node (ref "PLED1") (pin "5") (pinfunction "C4LG_5") (pintype "passive"))
      (node (ref "PLED2SENP") (pin "15") (pinfunction "A3RG_15") (pintype "passive"))
      (node (ref "PLED2SENP") (pin "27") (pinfunction "B3RG_27") (pintype "passive"))
      (node (ref "PLED2SENP") (pin "3") (pinfunction "G3RG_3") (pintype "passive"))
      (node (ref "R2") (pin "1") (pinfunction "1_1") (pintype "passive"))
    )
    (net (code "55") (name "Net-(PLED1-C4RG)") (class "Default")
      (node (ref "PLED1") (pin "19") (pinfunction "D4RG_19") (pintype "passive"))
      (node (ref "PLED1") (pin "31") (pinfunction "E4RG_31") (pintype "passive"))
      (node (ref "PLED1") (pin "43") (pinfunction "F4RG_43") (pintype "passive"))
      (node (ref "PLED1") (pin "7") (pinfunction "C4RG_7") (pintype "passive"))
      (node (ref "PLED2SENP") (pin "17") (pinfunction "A4LG_17") (pintype "passive"))
      (node (ref "PLED2SENP") (pin "29") (pinfunction "B4LG_29") (pintype "passive"))
      (node (ref "PLED2SENP") (pin "5") (pinfunction "G4LG_5") (pintype "passive"))
      (node (ref "R3") (pin "1") (pinfunction "1_1") (pintype "passive"))
    )
    (net (code "56") (name "Net-(PLED1-C5LG)") (class "Default")
      (node (ref "PLED1") (pin "21") (pinfunction "D5LG_21") (pintype "passive"))
      (node (ref "PLED1") (pin "33") (pinfunction "E5LG_33") (pintype "passive"))
      (node (ref "PLED1") (pin "45") (pinfunction "F5LG_45") (pintype "passive"))
      (node (ref "PLED1") (pin "9") (pinfunction "C5LG_9") (pintype "passive"))
      (node (ref "PLED2SENP") (pin "19") (pinfunction "A4RG_19") (pintype "passive"))
      (node (ref "PLED2SENP") (pin "31") (pinfunction "B4RG_31") (pintype "passive"))
      (node (ref "PLED2SENP") (pin "7") (pinfunction "G4RG_7") (pintype "passive"))
      (node (ref "R4") (pin "1") (pinfunction "1_1") (pintype "passive"))
    )
    (net (code "57") (name "Net-(PLED1-C5RG)") (class "Default")
      (node (ref "PLED1") (pin "11") (pinfunction "C5RG_11") (pintype "passive"))
      (node (ref "PLED1") (pin "23") (pinfunction "D5RG_23") (pintype "passive"))
      (node (ref "PLED1") (pin "35") (pinfunction "E5RG_35") (pintype "passive"))
      (node (ref "PLED1") (pin "47") (pinfunction "F5RG_47") (pintype "passive"))
      (node (ref "PLED2SENP") (pin "21") (pinfunction "A5LG_21") (pintype "passive"))
      (node (ref "PLED2SENP") (pin "33") (pinfunction "B5LG_33") (pintype "passive"))
      (node (ref "PLED2SENP") (pin "9") (pinfunction "G5LG_9") (pintype "passive"))
      (node (ref "R5") (pin "1") (pinfunction "1_1") (pintype "passive"))
    )
    (net (code "58") (name "Net-(PLED1-D3LG)") (class "Default")
      (node (ref "PLED1") (pin "13") (pinfunction "D3LG_13") (pintype "passive"))
      (node (ref "PLED1") (pin "25") (pinfunction "E3LG_25") (pintype "passive"))
      (node (ref "PLED1") (pin "37") (pinfunction "F3LG_37") (pintype "passive"))
      (node (ref "PLED1") (pin "49") (pinfunction "49_49") (pintype "passive"))
      (node (ref "PLED2SENP") (pin "11") (pinfunction "G5RG_11") (pintype "passive"))
      (node (ref "PLED2SENP") (pin "23") (pinfunction "A5RG_23") (pintype "passive"))
      (node (ref "PLED2SENP") (pin "35") (pinfunction "B5RG_35") (pintype "passive"))
      (node (ref "R6") (pin "1") (pinfunction "1_1") (pintype "passive"))
    )
    (net (code "59") (name "Net-(R3Sel-D)") (class "Default")
      (node (ref "R2") (pin "2") (pinfunction "2_2") (pintype "passive"))
      (node (ref "R3Sel") (pin "2") (pinfunction "D_2") (pintype "passive"))
    )
    (net (code "60") (name "Net-(R4Sel-D)") (class "Default")
      (node (ref "R4") (pin "2") (pinfunction "2_2") (pintype "passive"))
      (node (ref "R4Sel") (pin "2") (pinfunction "D_2") (pintype "passive"))
    )
    (net (code "61") (name "Net-(R5Sel-D)") (class "Default")
      (node (ref "R5Sel") (pin "2") (pinfunction "D_2") (pintype "passive"))
      (node (ref "R6") (pin "2") (pinfunction "2_2") (pintype "passive"))
    )
    (net (code "62") (name "VCC") (class "Default")
      (node (ref "C1") (pin "2") (pinfunction "2_2") (pintype "passive"))
      (node (ref "C2") (pin "1") (pinfunction "1_1") (pintype "passive"))
      (node (ref "PIC18F2682") (pin "20") (pinfunction "Vdd_20") (pintype "power_in"))
      (node (ref "PPIC2") (pin "9") (pinfunction "9_9") (pintype "passive"))
    )
    (net (code "63") (name "unconnected-(AR4-OS_NUL-Pad5)") (class "Default")
      (node (ref "AR4") (pin "5") (pinfunction "OS_NUL_5") (pintype "passive"))
    )
    (net (code "64") (name "unconnected-(AR4-OUT-Pad6)") (class "Default")
      (node (ref "AR4") (pin "6") (pinfunction "OUT_6") (pintype "output"))
    )
    (net (code "65") (name "unconnected-(AR4-V+-Pad7)") (class "Default")
      (node (ref "AR4") (pin "7") (pinfunction "V+_7") (pintype "power_in"))
    )
    (net (code "66") (name "unconnected-(PLED1-C3LG-Pad1)") (class "Default")
      (node (ref "PLED1") (pin "1") (pinfunction "C3LG_1") (pintype "passive"))
    )
    (net (code "67") (name "unconnected-(PLED1-C3LV-Pad2)") (class "Default")
      (node (ref "PLED1") (pin "2") (pinfunction "C3LV_2") (pintype "passive"))
    )
    (net (code "68") (name "unconnected-(PLED2SENP-Pad37)") (class "Default")
      (node (ref "PLED2SENP") (pin "37") (pinfunction "37_37") (pintype "passive"))
    )
    (net (code "69") (name "unconnected-(PLED2SENP-Pad38)") (class "Default")
      (node (ref "PLED2SENP") (pin "38") (pinfunction "38_38") (pintype "passive"))
    )
    (net (code "70") (name "unconnected-(PLED2SENP-Pad39)") (class "Default")
      (node (ref "PLED2SENP") (pin "39") (pinfunction "39_39") (pintype "passive"))
    )
    (net (code "71") (name "unconnected-(PLED2SENP-Pad40)") (class "Default")
      (node (ref "PLED2SENP") (pin "40") (pinfunction "40_40") (pintype "passive"))
    )
    (net (code "72") (name "unconnected-(PLED2SENP-Pad41)") (class "Default")
      (node (ref "PLED2SENP") (pin "41") (pinfunction "41_41") (pintype "passive"))
    )
    (net (code "73") (name "unconnected-(PLED2SENP-Pad42)") (class "Default")
      (node (ref "PLED2SENP") (pin "42") (pinfunction "42_42") (pintype "passive"))
    )
    (net (code "74") (name "unconnected-(PLED2SENP-Pad43)") (class "Default")
      (node (ref "PLED2SENP") (pin "43") (pinfunction "43_43") (pintype "passive"))
    )
    (net (code "75") (name "unconnected-(PLED2SENP-Pad44)") (class "Default")
      (node (ref "PLED2SENP") (pin "44") (pinfunction "44_44") (pintype "passive"))
    )
    (net (code "76") (name "unconnected-(PLED2SENP-Pad45)") (class "Default")
      (node (ref "PLED2SENP") (pin "45") (pinfunction "45_45") (pintype "passive"))
    )
    (net (code "77") (name "unconnected-(PLED2SENP-Pad46)") (class "Default")
      (node (ref "PLED2SENP") (pin "46") (pinfunction "46_46") (pintype "passive"))
    )
    (net (code "78") (name "unconnected-(PLED2SENP-Pad47)") (class "Default")
      (node (ref "PLED2SENP") (pin "47") (pinfunction "47_47") (pintype "passive"))
    )
    (net (code "79") (name "unconnected-(PLED2SENP-Pad48)") (class "Default")
      (node (ref "PLED2SENP") (pin "48") (pinfunction "48_48") (pintype "passive"))
    )
    (net (code "80") (name "unconnected-(PLED2SENP-Pad49)") (class "Default")
      (node (ref "PLED2SENP") (pin "49") (pinfunction "49_49") (pintype "passive"))
    )
    (net (code "81") (name "unconnected-(PLED2SENP-Pad50)") (class "Default")
      (node (ref "PLED2SENP") (pin "50") (pinfunction "50_50") (pintype "passive"))
    )
    (net (code "82") (name "unconnected-(R4Sel-G-Pad1)") (class "Default")
      (node (ref "R4Sel") (pin "1") (pinfunction "G_1") (pintype "passive"))
    )
  )
)
